# GRLV_double_Rail_v0_3_P2.net
KiCad netlist of a schematic drawn in Altium Designer
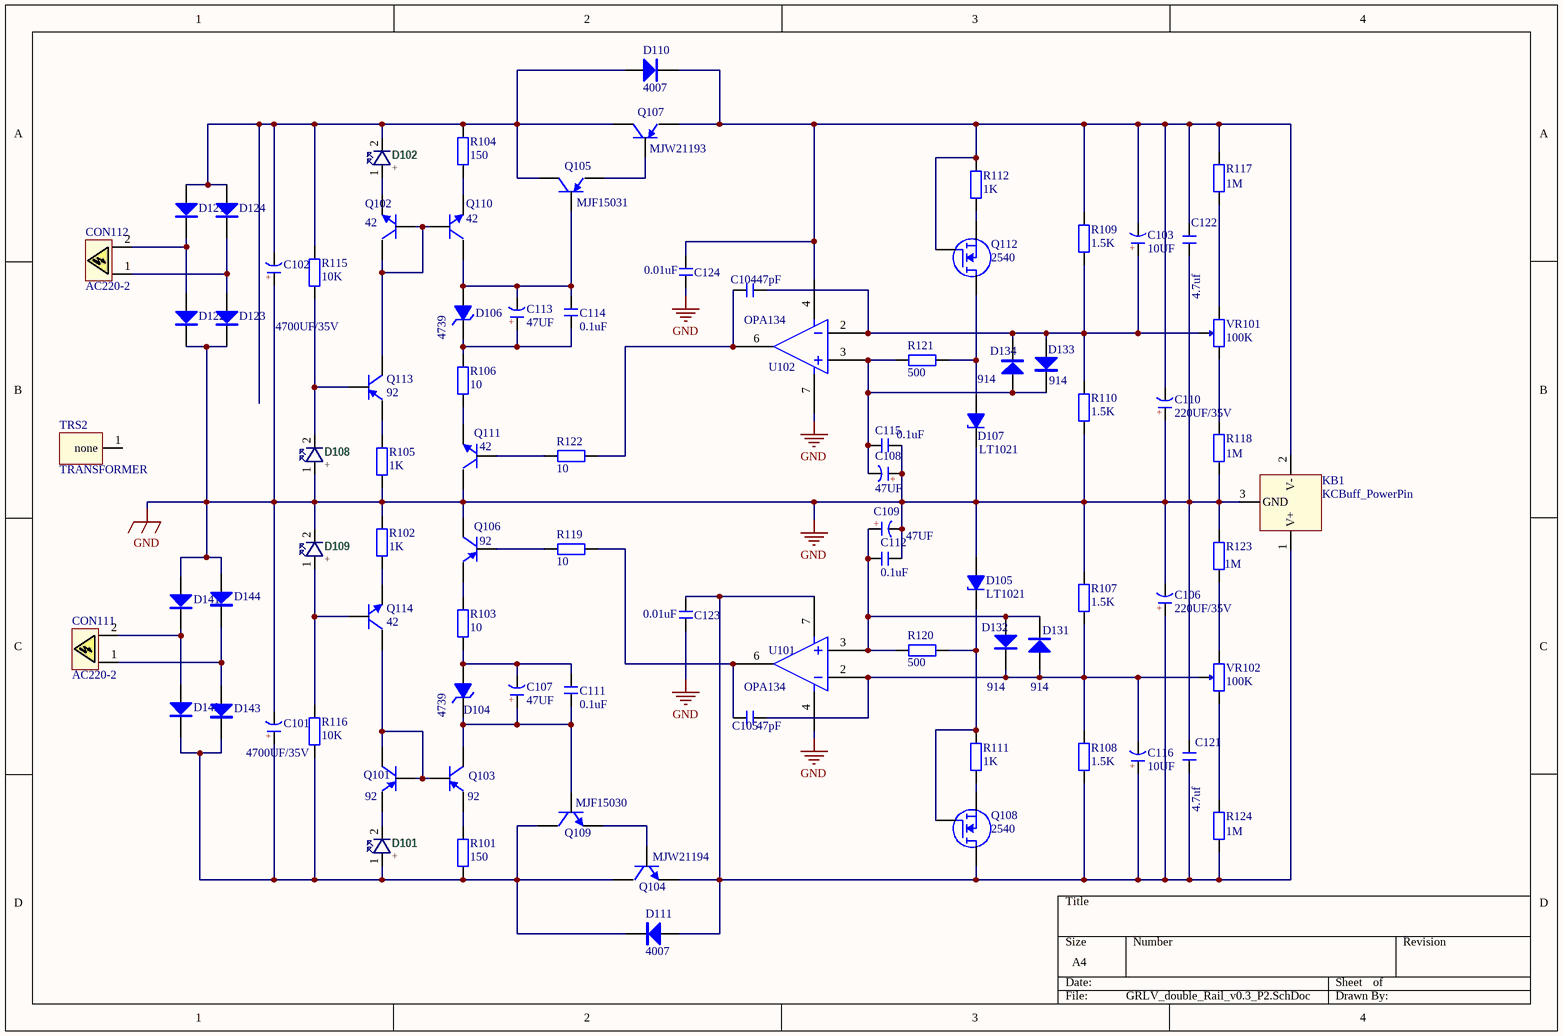
[diagram p0: GRLV_double_Rail_v0.3_P2.SchDoc]

(export (version "E")
  (design (tool "Eeschema 10.0.6"))
  (components
    (comp (ref "C101")
      (value "4700UF/35V")
      (footprint "CAP 10*22*31.5 - BK")
      (description "直插电解电容")
      (fields (field (name "版权归属") "源创客"))
      (libsource (lib "电阻-电容-电感") (part "C-CAP"))
    )
    (comp (ref "C102")
      (value "4700UF/35V")
      (footprint "CAP 10*22*31.5 - BK")
      (description "直插电解电容")
      (fields (field (name "版权归属") "源创客"))
      (libsource (lib "电阻-电容-电感") (part "C-CAP"))
    )
    (comp (ref "C103")
      (value "10UF")
      (footprint "CAP 2.5*6.3*7")
      (description "直插电解电容")
      (fields (field (name "版权归属") "源创客"))
      (libsource (lib "电阻-电容-电感") (part "C-CAP"))
    )
    (comp (ref "C104")
      (value "47pF")
      (footprint "CBB 6.3*6.3*5")
      (description "CBB电容")
      (fields (field (name "版权归属") "源创客"))
      (libsource (lib "电阻-电容-电感") (part "C-CBB"))
    )
    (comp (ref "C105")
      (value "47pF")
      (footprint "CBB 6.3*6.3*5")
      (description "CBB电容")
      (fields (field (name "版权归属") "源创客"))
      (libsource (lib "电阻-电容-电感") (part "C-CBB"))
    )
    (comp (ref "C106")
      (value "220UF/35V")
      (footprint "CAP 5.0*10*12.5")
      (description "直插电解电容")
      (fields (field (name "版权归属") "源创客"))
      (libsource (lib "电阻-电容-电感") (part "C-CAP"))
    )
    (comp (ref "C107")
      (value "47UF")
      (footprint "CAP 3.5*8*11.5")
      (description "直插电解电容")
      (fields (field (name "版权归属") "源创客"))
      (libsource (lib "电阻-电容-电感") (part "C-CAP"))
    )
    (comp (ref "C108")
      (value "47UF")
      (footprint "CAP 2.5*6.3*11.2")
      (description "直插电解电容")
      (fields (field (name "版权归属") "源创客"))
      (libsource (lib "") (part "C-CAP_1"))
    )
    (comp (ref "C109")
      (value "47UF")
      (footprint "CAP 2.5*6.3*11.2")
      (description "直插电解电容")
      (fields (field (name "版权归属") "源创客"))
      (libsource (lib "") (part "C-CAP_1"))
    )
    (comp (ref "C110")
      (value "220UF/35V")
      (footprint "CAP 5.0*10*12.5")
      (description "直插电解电容")
      (fields (field (name "版权归属") "源创客"))
      (libsource (lib "电阻-电容-电感") (part "C-CAP"))
    )
    (comp (ref "C111")
      (value "0.1uF")
      (footprint "CBB 6.3*6.3*5")
      (description "CBB电容")
      (fields (field (name "版权归属") "源创客"))
      (libsource (lib "电阻-电容-电感") (part "C-CBB"))
    )
    (comp (ref "C112")
      (value "0.1uF")
      (footprint "CBB 6.3*6.3*5")
      (description "CBB电容")
      (fields (field (name "版权归属") "源创客"))
      (libsource (lib "电阻-电容-电感") (part "C-CBB"))
    )
    (comp (ref "C113")
      (value "47UF")
      (footprint "CAP 3.5*8*11.5")
      (description "直插电解电容")
      (fields (field (name "版权归属") "源创客"))
      (libsource (lib "电阻-电容-电感") (part "C-CAP"))
    )
    (comp (ref "C114")
      (value "0.1uF")
      (footprint "CBB 6.3*6.3*5")
      (description "CBB电容")
      (fields (field (name "版权归属") "源创客"))
      (libsource (lib "电阻-电容-电感") (part "C-CBB"))
    )
    (comp (ref "C115")
      (value "0.1uF")
      (footprint "CBB 6.3*6.3*5")
      (description "CBB电容")
      (fields (field (name "版权归属") "源创客"))
      (libsource (lib "电阻-电容-电感") (part "C-CBB"))
    )
    (comp (ref "C116")
      (value "10UF")
      (footprint "CAP 2.5*6.3*7")
      (description "直插电解电容")
      (fields (field (name "版权归属") "源创客"))
      (libsource (lib "电阻-电容-电感") (part "C-CAP"))
    )
    (comp (ref "C121")
      (value "4.7uf")
      (footprint "CBB 7.2*7.2*13")
      (description "MKS薄膜电容")
      (libsource (lib "电阻-电容-电感") (part "C-MKS"))
    )
    (comp (ref "C122")
      (value "4.7uf")
      (footprint "CBB 7.2*7.2*13")
      (description "MKS薄膜电容")
      (libsource (lib "电阻-电容-电感") (part "C-MKS"))
    )
    (comp (ref "C123")
      (value "0.01uF")
      (footprint "CBB 6.3*6.3*5")
      (description "CBB电容")
      (fields (field (name "Comment") ".01") (field (name "版权归属") "源创客"))
      (libsource (lib "电阻-电容-电感") (part "C-CBB"))
    )
    (comp (ref "C124")
      (value "0.01uF")
      (footprint "CBB 6.3*6.3*5")
      (description "CBB电容")
      (fields (field (name "Comment") ".01") (field (name "版权归属") "源创客"))
      (libsource (lib "电阻-电容-电感") (part "C-CBB"))
    )
    (comp (ref "CON111")
      (value "AC220-2")
      (footprint "HX4.0-2XS")
      (libsource (lib "Connectors") (part "AC220-2"))
    )
    (comp (ref "CON112")
      (value "AC220-2")
      (footprint "HX4.0-2XS")
      (libsource (lib "Connectors") (part "AC220-2"))
    )
    (comp (ref "D101")
      (value "+")
      (footprint "LED 3MM-R")
      (description "直插式LED")
      (libsource (lib "LED") (part "LED"))
    )
    (comp (ref "D102")
      (value "+")
      (footprint "LED 3MM-R")
      (description "直插式LED")
      (libsource (lib "LED") (part "LED"))
    )
    (comp (ref "D104")
      (value "4739")
      (footprint "DO-41")
      (description "9.1V/1W稳压管")
      (libsource (lib "二极管-整流桥") (part "1N4739"))
    )
    (comp (ref "D105")
      (value "LT1021")
      (footprint "DIP8-300_MH")
      (description "10V Precision Reference 2 Pin Config")
      (libsource (lib "电压参考") (part "LT1021-10-2P"))
    )
    (comp (ref "D106")
      (value "4739")
      (footprint "DO-41")
      (description "9.1V/1W稳压管")
      (libsource (lib "二极管-整流桥") (part "1N4739"))
    )
    (comp (ref "D107")
      (value "LT1021")
      (footprint "DIP8-300_MH")
      (description "10V Precision Reference 2 Pin Config")
      (libsource (lib "电压参考") (part "LT1021-10-2P"))
    )
    (comp (ref "D108")
      (value "+")
      (footprint "LED 3MM-R")
      (description "直插式LED")
      (libsource (lib "LED") (part "LED"))
    )
    (comp (ref "D109")
      (value "+")
      (footprint "LED 3MM-R")
      (description "直插式LED")
      (libsource (lib "LED") (part "LED"))
    )
    (comp (ref "D110")
      (value "4007")
      (footprint "DO-41")
      (description "整流二极管")
      (fields (field (name "版权归属") "源创客"))
      (libsource (lib "二极管-整流桥") (part "1N4007"))
    )
    (comp (ref "D111")
      (value "4007")
      (footprint "DO-41")
      (description "整流二极管")
      (fields (field (name "版权归属") "源创客"))
      (libsource (lib "二极管-整流桥") (part "1N4007"))
    )
    (comp (ref "D121")
      (value "VS-HFA08TB60-M3")
      (footprint "DO-15XL")
      (description "Ultrafast Soft Recovery Diado 8A 600V")
      (libsource (lib "二极管-整流桥") (part "VS-HFA08TB60-M3"))
    )
    (comp (ref "D122")
      (value "VS-HFA08TB60-M3")
      (footprint "DO-15XL")
      (description "Ultrafast Soft Recovery Diado 8A 600V")
      (libsource (lib "二极管-整流桥") (part "VS-HFA08TB60-M3"))
    )
    (comp (ref "D123")
      (value "VS-HFA08TB60-M3")
      (footprint "DO-15XL")
      (description "Ultrafast Soft Recovery Diado 8A 600V")
      (libsource (lib "二极管-整流桥") (part "VS-HFA08TB60-M3"))
    )
    (comp (ref "D124")
      (value "VS-HFA08TB60-M3")
      (footprint "DO-15XL")
      (description "Ultrafast Soft Recovery Diado 8A 600V")
      (libsource (lib "二极管-整流桥") (part "VS-HFA08TB60-M3"))
    )
    (comp (ref "D131")
      (value "914")
      (footprint "DO-35")
      (description "高速开关管 1V/0.25W")
      (libsource (lib "二极管-整流桥") (part "1N914"))
    )
    (comp (ref "D132")
      (value "914")
      (footprint "DO-35")
      (description "高速开关管 1V/0.25W")
      (libsource (lib "二极管-整流桥") (part "1N914"))
    )
    (comp (ref "D133")
      (value "914")
      (footprint "DO-35")
      (description "高速开关管 1V/0.25W")
      (libsource (lib "二极管-整流桥") (part "1N914"))
    )
    (comp (ref "D134")
      (value "914")
      (footprint "DO-35")
      (description "高速开关管 1V/0.25W")
      (libsource (lib "二极管-整流桥") (part "1N914"))
    )
    (comp (ref "D141")
      (value "VS-HFA08TB60-M3")
      (footprint "DO-15XL")
      (description "Ultrafast Soft Recovery Diado 8A 600V")
      (libsource (lib "二极管-整流桥") (part "VS-HFA08TB60-M3"))
    )
    (comp (ref "D142")
      (value "VS-HFA08TB60-M3")
      (footprint "DO-15XL")
      (description "Ultrafast Soft Recovery Diado 8A 600V")
      (libsource (lib "二极管-整流桥") (part "VS-HFA08TB60-M3"))
    )
    (comp (ref "D143")
      (value "VS-HFA08TB60-M3")
      (footprint "DO-15XL")
      (description "Ultrafast Soft Recovery Diado 8A 600V")
      (libsource (lib "二极管-整流桥") (part "VS-HFA08TB60-M3"))
    )
    (comp (ref "D144")
      (value "VS-HFA08TB60-M3")
      (footprint "DO-15XL")
      (description "Ultrafast Soft Recovery Diado 8A 600V")
      (libsource (lib "二极管-整流桥") (part "VS-HFA08TB60-M3"))
    )
    (comp (ref "KB1")
      (value "KCBuff_PowerPin")
      (footprint "KCBuff_PowerPin_M2.0")
      (description "King Cello Buffer Stage")
      (libsource (lib "KC_amp") (part "KCBuff_PowerPin"))
    )
    (comp (ref "Q101")
      (value "92")
      (footprint "TO92A")
      (description "High Voltage PNP Transistor")
      (libsource (lib "三极管") (part "KSP92/93"))
    )
    (comp (ref "Q102")
      (value "42")
      (footprint "TO92A")
      (description "High Voltage NPN Transistor")
      (libsource (lib "三极管") (part "KSP42/43"))
    )
    (comp (ref "Q103")
      (value "92")
      (footprint "TO92A")
      (description "High Voltage PNP Transistor")
      (libsource (lib "三极管") (part "KSP92/93"))
    )
    (comp (ref "Q104")
      (value "MJW21194")
      (footprint "TO247V")
      (description "Power NPN Transistor")
      (libsource (lib "三极管") (part "MJW21194"))
    )
    (comp (ref "Q105")
      (value "MJF15031")
      (footprint "TO220V")
      (description "Power PNP Transistor")
      (libsource (lib "三极管") (part "MJF15031"))
    )
    (comp (ref "Q106")
      (value "92")
      (footprint "TO92A")
      (description "High Voltage PNP Transistor")
      (libsource (lib "三极管") (part "KSP92/93"))
    )
    (comp (ref "Q107")
      (value "MJW21193")
      (footprint "TO247V")
      (description "Power PNP Transistor")
      (libsource (lib "三极管") (part "MJW21193"))
    )
    (comp (ref "Q108")
      (value "2540")
      (footprint "TO92A")
      (description "N沟道耗尽型DMOS场效应管 400V/150ma")
      (libsource (lib "场效应管") (part "DN2540"))
    )
    (comp (ref "Q109")
      (value "MJF15030")
      (footprint "TO220V")
      (description "Power NPN Transistor")
      (libsource (lib "三极管") (part "MJF15030"))
    )
    (comp (ref "Q110")
      (value "42")
      (footprint "TO92A")
      (description "High Voltage NPN Transistor")
      (libsource (lib "三极管") (part "KSP42/43"))
    )
    (comp (ref "Q111")
      (value "42")
      (footprint "TO92A")
      (description "High Voltage NPN Transistor")
      (libsource (lib "三极管") (part "KSP42/43"))
    )
    (comp (ref "Q112")
      (value "2540")
      (footprint "TO92A")
      (description "N沟道耗尽型DMOS场效应管 400V/150ma")
      (libsource (lib "场效应管") (part "DN2540"))
    )
    (comp (ref "Q113")
      (value "92")
      (footprint "TO92A")
      (description "High Voltage PNP Transistor")
      (libsource (lib "三极管") (part "KSP92/93"))
    )
    (comp (ref "Q114")
      (value "42")
      (footprint "TO92A")
      (description "High Voltage NPN Transistor")
      (libsource (lib "三极管") (part "KSP42/43"))
    )
    (comp (ref "R101")
      (value "150")
      (footprint "RS 1/4W")
      (description "直插色环电阻")
      (fields (field (name "版权归属") "源创客"))
      (libsource (lib "电阻-电容-电感") (part "R-CRR"))
    )
    (comp (ref "R102")
      (value "1K")
      (footprint "RS 1/4W")
      (description "直插色环电阻")
      (fields (field (name "版权归属") "源创客"))
      (libsource (lib "电阻-电容-电感") (part "R-CRR"))
    )
    (comp (ref "R103")
      (value "10")
      (footprint "RS 1/4W")
      (description "直插色环电阻")
      (fields (field (name "版权归属") "源创客"))
      (libsource (lib "电阻-电容-电感") (part "R-CRR"))
    )
    (comp (ref "R104")
      (value "150")
      (footprint "RS 1/4W")
      (description "直插色环电阻")
      (fields (field (name "版权归属") "源创客"))
      (libsource (lib "电阻-电容-电感") (part "R-CRR"))
    )
    (comp (ref "R105")
      (value "1K")
      (footprint "RS 1/4W")
      (description "直插色环电阻")
      (fields (field (name "版权归属") "源创客"))
      (libsource (lib "电阻-电容-电感") (part "R-CRR"))
    )
    (comp (ref "R106")
      (value "10")
      (footprint "RS 1/4W")
      (description "直插色环电阻")
      (fields (field (name "版权归属") "源创客"))
      (libsource (lib "电阻-电容-电感") (part "R-CRR"))
    )
    (comp (ref "R107")
      (value "1.5K")
      (footprint "RS 1/4W")
      (description "直插色环电阻")
      (fields (field (name "版权归属") "源创客"))
      (libsource (lib "电阻-电容-电感") (part "R-CRR"))
    )
    (comp (ref "R108")
      (value "1.5K")
      (footprint "RS 1/4W")
      (description "直插色环电阻")
      (fields (field (name "版权归属") "源创客"))
      (libsource (lib "电阻-电容-电感") (part "R-CRR"))
    )
    (comp (ref "R109")
      (value "1.5K")
      (footprint "RS 1/4W")
      (description "直插色环电阻")
      (fields (field (name "版权归属") "源创客"))
      (libsource (lib "电阻-电容-电感") (part "R-CRR"))
    )
    (comp (ref "R110")
      (value "1.5K")
      (footprint "RS 1/4W")
      (description "直插色环电阻")
      (fields (field (name "版权归属") "源创客"))
      (libsource (lib "电阻-电容-电感") (part "R-CRR"))
    )
    (comp (ref "R111")
      (value "1K")
      (footprint "RS 1/4W")
      (description "直插色环电阻")
      (fields (field (name "版权归属") "源创客"))
      (libsource (lib "电阻-电容-电感") (part "R-CRR"))
    )
    (comp (ref "R112")
      (value "1K")
      (footprint "RS 1/4W")
      (description "直插色环电阻")
      (fields (field (name "版权归属") "源创客"))
      (libsource (lib "电阻-电容-电感") (part "R-CRR"))
    )
    (comp (ref "R115")
      (value "10K")
      (footprint "RS 1/4W")
      (description "直插色环电阻")
      (fields (field (name "版权归属") "源创客"))
      (libsource (lib "电阻-电容-电感") (part "R-CRR"))
    )
    (comp (ref "R116")
      (value "10K")
      (footprint "RS 1/4W")
      (description "直插色环电阻")
      (fields (field (name "版权归属") "源创客"))
      (libsource (lib "电阻-电容-电感") (part "R-CRR"))
    )
    (comp (ref "R117")
      (value "1M")
      (footprint "RS 1/4W")
      (description "直插色环电阻")
      (fields (field (name "版权归属") "源创客"))
      (libsource (lib "电阻-电容-电感") (part "R-CRR"))
    )
    (comp (ref "R118")
      (value "1M")
      (footprint "RS 1/4W")
      (description "直插色环电阻")
      (fields (field (name "版权归属") "源创客"))
      (libsource (lib "电阻-电容-电感") (part "R-CRR"))
    )
    (comp (ref "R119")
      (value "10")
      (footprint "RS 1/4W")
      (description "直插色环电阻")
      (fields (field (name "版权归属") "源创客"))
      (libsource (lib "电阻-电容-电感") (part "R-CRR"))
    )
    (comp (ref "R120")
      (value "500")
      (footprint "RS 1/4W")
      (description "直插色环电阻")
      (fields (field (name "版权归属") "源创客"))
      (libsource (lib "电阻-电容-电感") (part "R-CRR"))
    )
    (comp (ref "R121")
      (value "500")
      (footprint "RS 1/4W")
      (description "直插色环电阻")
      (fields (field (name "版权归属") "源创客"))
      (libsource (lib "电阻-电容-电感") (part "R-CRR"))
    )
    (comp (ref "R122")
      (value "10")
      (footprint "RS 1/4W")
      (description "直插色环电阻")
      (fields (field (name "版权归属") "源创客"))
      (libsource (lib "电阻-电容-电感") (part "R-CRR"))
    )
    (comp (ref "R123")
      (value "1M")
      (footprint "RS 1/4W")
      (description "直插色环电阻")
      (fields (field (name "版权归属") "源创客"))
      (libsource (lib "电阻-电容-电感") (part "R-CRR"))
    )
    (comp (ref "R124")
      (value "1M")
      (footprint "RS 1/4W")
      (description "直插色环电阻")
      (fields (field (name "版权归属") "源创客"))
      (libsource (lib "电阻-电容-电感") (part "R-CRR"))
    )
    (comp (ref "TRS2")
      (value "TRANSFORMER")
      (footprint "TRANS_BLOCK_m4_68mm")
      (description "Transformer")
      (libsource (lib "KC_amp") (part "TRANSFORMER"))
    )
    (comp (ref "U101") (value "OPA134") (footprint "DIP8-300_MH") (libsource (lib "运放") (part "OPA134PA")))
    (comp (ref "U102") (value "OPA134") (footprint "DIP8-300_MH") (libsource (lib "运放") (part "OPA134PA")))
    (comp (ref "VR101")
      (value "100K")
      (footprint "RS 1/2W-VR")
      (description "直插可调电阻-顶调")
      (libsource (lib "电阻-电容-电感") (part "VR-W"))
    )
    (comp (ref "VR102")
      (value "100K")
      (footprint "RS 1/2W-VR")
      (description "直插可调电阻-顶调")
      (libsource (lib "电阻-电容-电感") (part "VR-W"))
    )
  )
  (nets
    (net (code "1") (name "GND") (class "Default")
      (node (ref "C101") (pin "2") (pinfunction "K_2") (pintype "passive"))
      (node (ref "C102") (pin "1") (pinfunction "A_1") (pintype "passive"))
      (node (ref "C106") (pin "2") (pinfunction "K_2") (pintype "passive"))
      (node (ref "C108") (pin "1") (pinfunction "A_1") (pintype "passive"))
      (node (ref "C109") (pin "2") (pinfunction "K_2") (pintype "passive"))
      (node (ref "C110") (pin "1") (pinfunction "A_1") (pintype "passive"))
      (node (ref "C112") (pin "2") (pinfunction "2_2") (pintype "passive"))
      (node (ref "C115") (pin "2") (pinfunction "2_2") (pintype "passive"))
      (node (ref "C121") (pin "2") (pinfunction "2_2") (pintype "passive"))
      (node (ref "C122") (pin "1") (pinfunction "1_1") (pintype "passive"))
      (node (ref "C123") (pin "1") (pinfunction "1_1") (pintype "passive"))
      (node (ref "C124") (pin "1") (pinfunction "1_1") (pintype "passive"))
      (node (ref "D105") (pin "4") (pinfunction "A_4") (pintype "passive"))
      (node (ref "D107") (pin "6") (pinfunction "K_6") (pintype "passive"))
      (node (ref "D108") (pin "1") (pinfunction "A_1") (pintype "passive"))
      (node (ref "D109") (pin "2") (pinfunction "K_2") (pintype "passive"))
      (node (ref "D122") (pin "1") (pinfunction "Cathode_1") (pintype "passive"))
      (node (ref "D123") (pin "1") (pinfunction "Cathode_1") (pintype "passive"))
      (node (ref "D141") (pin "2") (pinfunction "Anode_2") (pintype "passive"))
      (node (ref "D144") (pin "2") (pinfunction "Anode_2") (pintype "passive"))
      (node (ref "KB1") (pin "3") (pinfunction "GND_3") (pintype "passive"))
      (node (ref "Q106") (pin "3") (pinfunction "C_3") (pintype "passive"))
      (node (ref "Q111") (pin "3") (pinfunction "C_3") (pintype "passive"))
      (node (ref "R102") (pin "2") (pinfunction "2_2") (pintype "passive"))
      (node (ref "R105") (pin "1") (pinfunction "1_1") (pintype "passive"))
      (node (ref "R107") (pin "2") (pinfunction "2_2") (pintype "passive"))
      (node (ref "R110") (pin "1") (pinfunction "1_1") (pintype "passive"))
      (node (ref "R118") (pin "1") (pinfunction "1_1") (pintype "passive"))
      (node (ref "R123") (pin "2") (pinfunction "2_2") (pintype "passive"))
      (node (ref "U101") (pin "4") (pinfunction "V-_4") (pintype "passive"))
      (node (ref "U102") (pin "7") (pinfunction "V+_7") (pintype "passive"))
    )
    (net (code "2") (name "Net-(C101-A)") (class "Default")
      (node (ref "C101") (pin "1") (pinfunction "A_1") (pintype "passive"))
      (node (ref "D101") (pin "1") (pinfunction "A_1") (pintype "passive"))
      (node (ref "D111") (pin "2") (pinfunction "K_2") (pintype "passive"))
      (node (ref "D142") (pin "1") (pinfunction "Cathode_1") (pintype "passive"))
      (node (ref "D143") (pin "1") (pinfunction "Cathode_1") (pintype "passive"))
      (node (ref "Q104") (pin "2") (pinfunction "C_2") (pintype "passive"))
      (node (ref "Q109") (pin "2") (pinfunction "C_2") (pintype "passive"))
      (node (ref "R101") (pin "1") (pinfunction "1_1") (pintype "passive"))
      (node (ref "R116") (pin "1") (pinfunction "1_1") (pintype "passive"))
    )
    (net (code "3") (name "Net-(C102-K)") (class "Default")
      (node (ref "C102") (pin "2") (pinfunction "K_2") (pintype "passive"))
      (node (ref "D102") (pin "2") (pinfunction "K_2") (pintype "passive"))
      (node (ref "D110") (pin "1") (pinfunction "A_1") (pintype "passive"))
      (node (ref "D121") (pin "2") (pinfunction "Anode_2") (pintype "passive"))
      (node (ref "D124") (pin "2") (pinfunction "Anode_2") (pintype "passive"))
      (node (ref "Q105") (pin "2") (pinfunction "C_2") (pintype "passive"))
      (node (ref "Q107") (pin "2") (pinfunction "C_2") (pintype "passive"))
      (node (ref "R104") (pin "2") (pinfunction "2_2") (pintype "passive"))
      (node (ref "R115") (pin "2") (pinfunction "2_2") (pintype "passive"))
    )
    (net (code "4") (name "Net-(C103-A)") (class "Default")
      (node (ref "C103") (pin "1") (pinfunction "A_1") (pintype "passive"))
      (node (ref "C104") (pin "2") (pinfunction "2_2") (pintype "passive"))
      (node (ref "D133") (pin "1") (pinfunction "A_1") (pintype "passive"))
      (node (ref "D134") (pin "2") (pinfunction "K_2") (pintype "passive"))
      (node (ref "R109") (pin "1") (pinfunction "1_1") (pintype "passive"))
      (node (ref "R110") (pin "2") (pinfunction "2_2") (pintype "passive"))
      (node (ref "U102") (pin "2") (pinfunction "-in_2") (pintype "passive"))
      (node (ref "VR101") (pin "3") (pinfunction "3_3") (pintype "passive"))
    )
    (net (code "5") (name "Net-(C103-K)") (class "Default")
      (node (ref "C103") (pin "2") (pinfunction "K_2") (pintype "passive"))
      (node (ref "C110") (pin "2") (pinfunction "K_2") (pintype "passive"))
      (node (ref "C122") (pin "2") (pinfunction "2_2") (pintype "passive"))
      (node (ref "C124") (pin "2") (pinfunction "2_2") (pintype "passive"))
      (node (ref "D110") (pin "2") (pinfunction "K_2") (pintype "passive"))
      (node (ref "KB1") (pin "2") (pinfunction "V-_2") (pintype "passive"))
      (node (ref "Q107") (pin "3") (pinfunction "E_3") (pintype "passive"))
      (node (ref "Q112") (pin "2") (pinfunction "G_2") (pintype "passive"))
      (node (ref "R109") (pin "2") (pinfunction "2_2") (pintype "passive"))
      (node (ref "R112") (pin "2") (pinfunction "2_2") (pintype "passive"))
      (node (ref "R117") (pin "2") (pinfunction "2_2") (pintype "passive"))
      (node (ref "U102") (pin "4") (pinfunction "V-_4") (pintype "passive"))
    )
    (net (code "6") (name "Net-(C106-A)") (class "Default")
      (node (ref "C106") (pin "1") (pinfunction "A_1") (pintype "passive"))
      (node (ref "C116") (pin "1") (pinfunction "A_1") (pintype "passive"))
      (node (ref "C121") (pin "1") (pinfunction "1_1") (pintype "passive"))
      (node (ref "C123") (pin "2") (pinfunction "2_2") (pintype "passive"))
      (node (ref "D111") (pin "1") (pinfunction "A_1") (pintype "passive"))
      (node (ref "KB1") (pin "1") (pinfunction "V+_1") (pintype "passive"))
      (node (ref "Q104") (pin "3") (pinfunction "E_3") (pintype "passive"))
      (node (ref "Q108") (pin "3") (pinfunction "D_3") (pintype "passive"))
      (node (ref "R108") (pin "1") (pinfunction "1_1") (pintype "passive"))
      (node (ref "R124") (pin "1") (pinfunction "1_1") (pintype "passive"))
      (node (ref "U101") (pin "7") (pinfunction "V+_7") (pintype "passive"))
    )
    (net (code "7") (name "Net-(C107-A)") (class "Default")
      (node (ref "C107") (pin "1") (pinfunction "A_1") (pintype "passive"))
      (node (ref "C111") (pin "1") (pinfunction "1_1") (pintype "passive"))
      (node (ref "D104") (pin "2") (pinfunction "K_2") (pintype "passive"))
      (node (ref "Q103") (pin "3") (pinfunction "C_3") (pintype "passive"))
      (node (ref "Q109") (pin "1") (pinfunction "B_1") (pintype "passive"))
    )
    (net (code "8") (name "Net-(C107-K)") (class "Default")
      (node (ref "C107") (pin "2") (pinfunction "K_2") (pintype "passive"))
      (node (ref "C111") (pin "2") (pinfunction "2_2") (pintype "passive"))
      (node (ref "D104") (pin "1") (pinfunction "A_1") (pintype "passive"))
      (node (ref "R103") (pin "1") (pinfunction "1_1") (pintype "passive"))
    )
    (net (code "9") (name "Net-(C108-K)") (class "Default")
      (node (ref "C108") (pin "2") (pinfunction "K_2") (pintype "passive"))
      (node (ref "C115") (pin "1") (pinfunction "1_1") (pintype "passive"))
      (node (ref "D133") (pin "2") (pinfunction "K_2") (pintype "passive"))
      (node (ref "D134") (pin "1") (pinfunction "A_1") (pintype "passive"))
      (node (ref "R121") (pin "1") (pinfunction "1_1") (pintype "passive"))
      (node (ref "U102") (pin "3") (pinfunction "+in_3") (pintype "passive"))
    )
    (net (code "10") (name "Net-(C109-A)") (class "Default")
      (node (ref "C109") (pin "1") (pinfunction "A_1") (pintype "passive"))
      (node (ref "C112") (pin "1") (pinfunction "1_1") (pintype "passive"))
      (node (ref "D131") (pin "2") (pinfunction "K_2") (pintype "passive"))
      (node (ref "D132") (pin "1") (pinfunction "A_1") (pintype "passive"))
      (node (ref "R120") (pin "1") (pinfunction "1_1") (pintype "passive"))
      (node (ref "U101") (pin "3") (pinfunction "+in_3") (pintype "passive"))
    )
    (net (code "11") (name "Net-(C113-A)") (class "Default")
      (node (ref "C113") (pin "1") (pinfunction "A_1") (pintype "passive"))
      (node (ref "C114") (pin "1") (pinfunction "1_1") (pintype "passive"))
      (node (ref "D106") (pin "2") (pinfunction "K_2") (pintype "passive"))
      (node (ref "R106") (pin "2") (pinfunction "2_2") (pintype "passive"))
    )
    (net (code "12") (name "Net-(C113-K)") (class "Default")
      (node (ref "C113") (pin "2") (pinfunction "K_2") (pintype "passive"))
      (node (ref "C114") (pin "2") (pinfunction "2_2") (pintype "passive"))
      (node (ref "D106") (pin "1") (pinfunction "A_1") (pintype "passive"))
      (node (ref "Q105") (pin "1") (pinfunction "B_1") (pintype "passive"))
      (node (ref "Q110") (pin "3") (pinfunction "C_3") (pintype "passive"))
    )
    (net (code "13") (name "Net-(C116-K)") (class "Default")
      (node (ref "C105") (pin "2") (pinfunction "2_2") (pintype "passive"))
      (node (ref "C116") (pin "2") (pinfunction "K_2") (pintype "passive"))
      (node (ref "D131") (pin "1") (pinfunction "A_1") (pintype "passive"))
      (node (ref "D132") (pin "2") (pinfunction "K_2") (pintype "passive"))
      (node (ref "R107") (pin "1") (pinfunction "1_1") (pintype "passive"))
      (node (ref "R108") (pin "2") (pinfunction "2_2") (pintype "passive"))
      (node (ref "U101") (pin "2") (pinfunction "-in_2") (pintype "passive"))
      (node (ref "VR102") (pin "3") (pinfunction "3_3") (pintype "passive"))
    )
    (net (code "14") (name "Net-(CON111-G)") (class "Default")
      (node (ref "CON111") (pin "2") (pinfunction "G_2") (pintype "passive"))
      (node (ref "D141") (pin "1") (pinfunction "Cathode_1") (pintype "passive"))
      (node (ref "D142") (pin "2") (pinfunction "Anode_2") (pintype "passive"))
    )
    (net (code "15") (name "Net-(CON111-L)") (class "Default")
      (node (ref "CON111") (pin "1") (pinfunction "L_1") (pintype "passive"))
      (node (ref "D143") (pin "2") (pinfunction "Anode_2") (pintype "passive"))
      (node (ref "D144") (pin "1") (pinfunction "Cathode_1") (pintype "passive"))
    )
    (net (code "16") (name "Net-(CON112-G)") (class "Default")
      (node (ref "CON112") (pin "2") (pinfunction "G_2") (pintype "passive"))
      (node (ref "D121") (pin "1") (pinfunction "Cathode_1") (pintype "passive"))
      (node (ref "D122") (pin "2") (pinfunction "Anode_2") (pintype "passive"))
    )
    (net (code "17") (name "Net-(CON112-L)") (class "Default")
      (node (ref "CON112") (pin "1") (pinfunction "L_1") (pintype "passive"))
      (node (ref "D123") (pin "2") (pinfunction "Anode_2") (pintype "passive"))
      (node (ref "D124") (pin "1") (pinfunction "Cathode_1") (pintype "passive"))
    )
    (net (code "18") (name "Net-(D101-K)") (class "Default")
      (node (ref "D101") (pin "2") (pinfunction "K_2") (pintype "passive"))
      (node (ref "Q101") (pin "1") (pinfunction "E_1") (pintype "passive"))
    )
    (net (code "19") (name "Net-(D102-A)") (class "Default")
      (node (ref "D102") (pin "1") (pinfunction "A_1") (pintype "passive"))
      (node (ref "Q102") (pin "1") (pinfunction "E_1") (pintype "passive"))
    )
    (net (code "20") (name "Net-(D105-K)") (class "Default")
      (node (ref "D105") (pin "6") (pinfunction "K_6") (pintype "passive"))
      (node (ref "Q108") (pin "2") (pinfunction "G_2") (pintype "passive"))
      (node (ref "R111") (pin "2") (pinfunction "2_2") (pintype "passive"))
      (node (ref "R120") (pin "2") (pinfunction "2_2") (pintype "passive"))
    )
    (net (code "21") (name "Net-(D107-A)") (class "Default")
      (node (ref "D107") (pin "4") (pinfunction "A_4") (pintype "passive"))
      (node (ref "Q112") (pin "3") (pinfunction "D_3") (pintype "passive"))
      (node (ref "R121") (pin "2") (pinfunction "2_2") (pintype "passive"))
    )
    (net (code "22") (name "Net-(D108-K)") (class "Default")
      (node (ref "D108") (pin "2") (pinfunction "K_2") (pintype "passive"))
      (node (ref "Q113") (pin "2") (pinfunction "B_2") (pintype "passive"))
      (node (ref "R115") (pin "1") (pinfunction "1_1") (pintype "passive"))
    )
    (net (code "23") (name "Net-(D109-A)") (class "Default")
      (node (ref "D109") (pin "1") (pinfunction "A_1") (pintype "passive"))
      (node (ref "Q114") (pin "2") (pinfunction "B_2") (pintype "passive"))
      (node (ref "R116") (pin "2") (pinfunction "2_2") (pintype "passive"))
    )
    (net (code "24") (name "Net-(Q101-B)") (class "Default")
      (node (ref "Q101") (pin "2") (pinfunction "B_2") (pintype "passive"))
      (node (ref "Q101") (pin "3") (pinfunction "C_3") (pintype "passive"))
      (node (ref "Q103") (pin "2") (pinfunction "B_2") (pintype "passive"))
      (node (ref "Q114") (pin "3") (pinfunction "C_3") (pintype "passive"))
    )
    (net (code "25") (name "Net-(Q102-B)") (class "Default")
      (node (ref "Q102") (pin "2") (pinfunction "B_2") (pintype "passive"))
      (node (ref "Q102") (pin "3") (pinfunction "C_3") (pintype "passive"))
      (node (ref "Q110") (pin "2") (pinfunction "B_2") (pintype "passive"))
      (node (ref "Q113") (pin "3") (pinfunction "C_3") (pintype "passive"))
    )
    (net (code "26") (name "Net-(Q103-E)") (class "Default")
      (node (ref "Q103") (pin "1") (pinfunction "E_1") (pintype "passive"))
      (node (ref "R101") (pin "2") (pinfunction "2_2") (pintype "passive"))
    )
    (net (code "27") (name "Net-(Q104-B)") (class "Default")
      (node (ref "Q104") (pin "1") (pinfunction "B_1") (pintype "passive"))
      (node (ref "Q109") (pin "3") (pinfunction "E_3") (pintype "passive"))
    )
    (net (code "28") (name "Net-(Q105-E)") (class "Default")
      (node (ref "Q105") (pin "3") (pinfunction "E_3") (pintype "passive"))
      (node (ref "Q107") (pin "1") (pinfunction "B_1") (pintype "passive"))
    )
    (net (code "29") (name "Net-(Q106-B)") (class "Default")
      (node (ref "Q106") (pin "2") (pinfunction "B_2") (pintype "passive"))
      (node (ref "R119") (pin "1") (pinfunction "1_1") (pintype "passive"))
    )
    (net (code "30") (name "Net-(Q106-E)") (class "Default")
      (node (ref "Q106") (pin "1") (pinfunction "E_1") (pintype "passive"))
      (node (ref "R103") (pin "2") (pinfunction "2_2") (pintype "passive"))
    )
    (net (code "31") (name "Net-(Q108-S)") (class "Default")
      (node (ref "Q108") (pin "1") (pinfunction "S_1") (pintype "passive"))
      (node (ref "R111") (pin "1") (pinfunction "1_1") (pintype "passive"))
    )
    (net (code "32") (name "Net-(Q110-E)") (class "Default")
      (node (ref "Q110") (pin "1") (pinfunction "E_1") (pintype "passive"))
      (node (ref "R104") (pin "1") (pinfunction "1_1") (pintype "passive"))
    )
    (net (code "33") (name "Net-(Q111-B)") (class "Default")
      (node (ref "Q111") (pin "2") (pinfunction "B_2") (pintype "passive"))
      (node (ref "R122") (pin "1") (pinfunction "1_1") (pintype "passive"))
    )
    (net (code "34") (name "Net-(Q111-E)") (class "Default")
      (node (ref "Q111") (pin "1") (pinfunction "E_1") (pintype "passive"))
      (node (ref "R106") (pin "1") (pinfunction "1_1") (pintype "passive"))
    )
    (net (code "35") (name "Net-(Q112-S)") (class "Default")
      (node (ref "Q112") (pin "1") (pinfunction "S_1") (pintype "passive"))
      (node (ref "R112") (pin "1") (pinfunction "1_1") (pintype "passive"))
    )
    (net (code "36") (name "Net-(Q113-E)") (class "Default")
      (node (ref "Q113") (pin "1") (pinfunction "E_1") (pintype "passive"))
      (node (ref "R105") (pin "2") (pinfunction "2_2") (pintype "passive"))
    )
    (net (code "37") (name "Net-(Q114-E)") (class "Default")
      (node (ref "Q114") (pin "1") (pinfunction "E_1") (pintype "passive"))
      (node (ref "R102") (pin "1") (pinfunction "1_1") (pintype "passive"))
    )
    (net (code "38") (name "Net-(R117-Pad1)") (class "Default")
      (node (ref "R117") (pin "1") (pinfunction "1_1") (pintype "passive"))
      (node (ref "VR101") (pin "2") (pinfunction "2_2") (pintype "passive"))
    )
    (net (code "39") (name "Net-(R118-Pad2)") (class "Default")
      (node (ref "R118") (pin "2") (pinfunction "2_2") (pintype "passive"))
      (node (ref "VR101") (pin "1") (pinfunction "1_1") (pintype "passive"))
    )
    (net (code "40") (name "Net-(R123-Pad1)") (class "Default")
      (node (ref "R123") (pin "1") (pinfunction "1_1") (pintype "passive"))
      (node (ref "VR102") (pin "2") (pinfunction "2_2") (pintype "passive"))
    )
    (net (code "41") (name "Net-(R124-Pad2)") (class "Default")
      (node (ref "R124") (pin "2") (pinfunction "2_2") (pintype "passive"))
      (node (ref "VR102") (pin "1") (pinfunction "1_1") (pintype "passive"))
    )
    (net (code "42") (name "Net-(U101-out)") (class "Default")
      (node (ref "C105") (pin "1") (pinfunction "1_1") (pintype "passive"))
      (node (ref "R119") (pin "2") (pinfunction "2_2") (pintype "passive"))
      (node (ref "U101") (pin "6") (pinfunction "out_6") (pintype "passive"))
    )
    (net (code "43") (name "Net-(U102-out)") (class "Default")
      (node (ref "C104") (pin "1") (pinfunction "1_1") (pintype "passive"))
      (node (ref "R122") (pin "2") (pinfunction "2_2") (pintype "passive"))
      (node (ref "U102") (pin "6") (pinfunction "out_6") (pintype "passive"))
    )
    (net (code "44") (name "unconnected-(TRS2-none-Pad1)") (class "Default")
      (node (ref "TRS2") (pin "1") (pinfunction "none_1") (pintype "passive"))
    )
  )
)
